# Test6502_project.net
KiCad netlist of a schematic drawn in Altium Designer
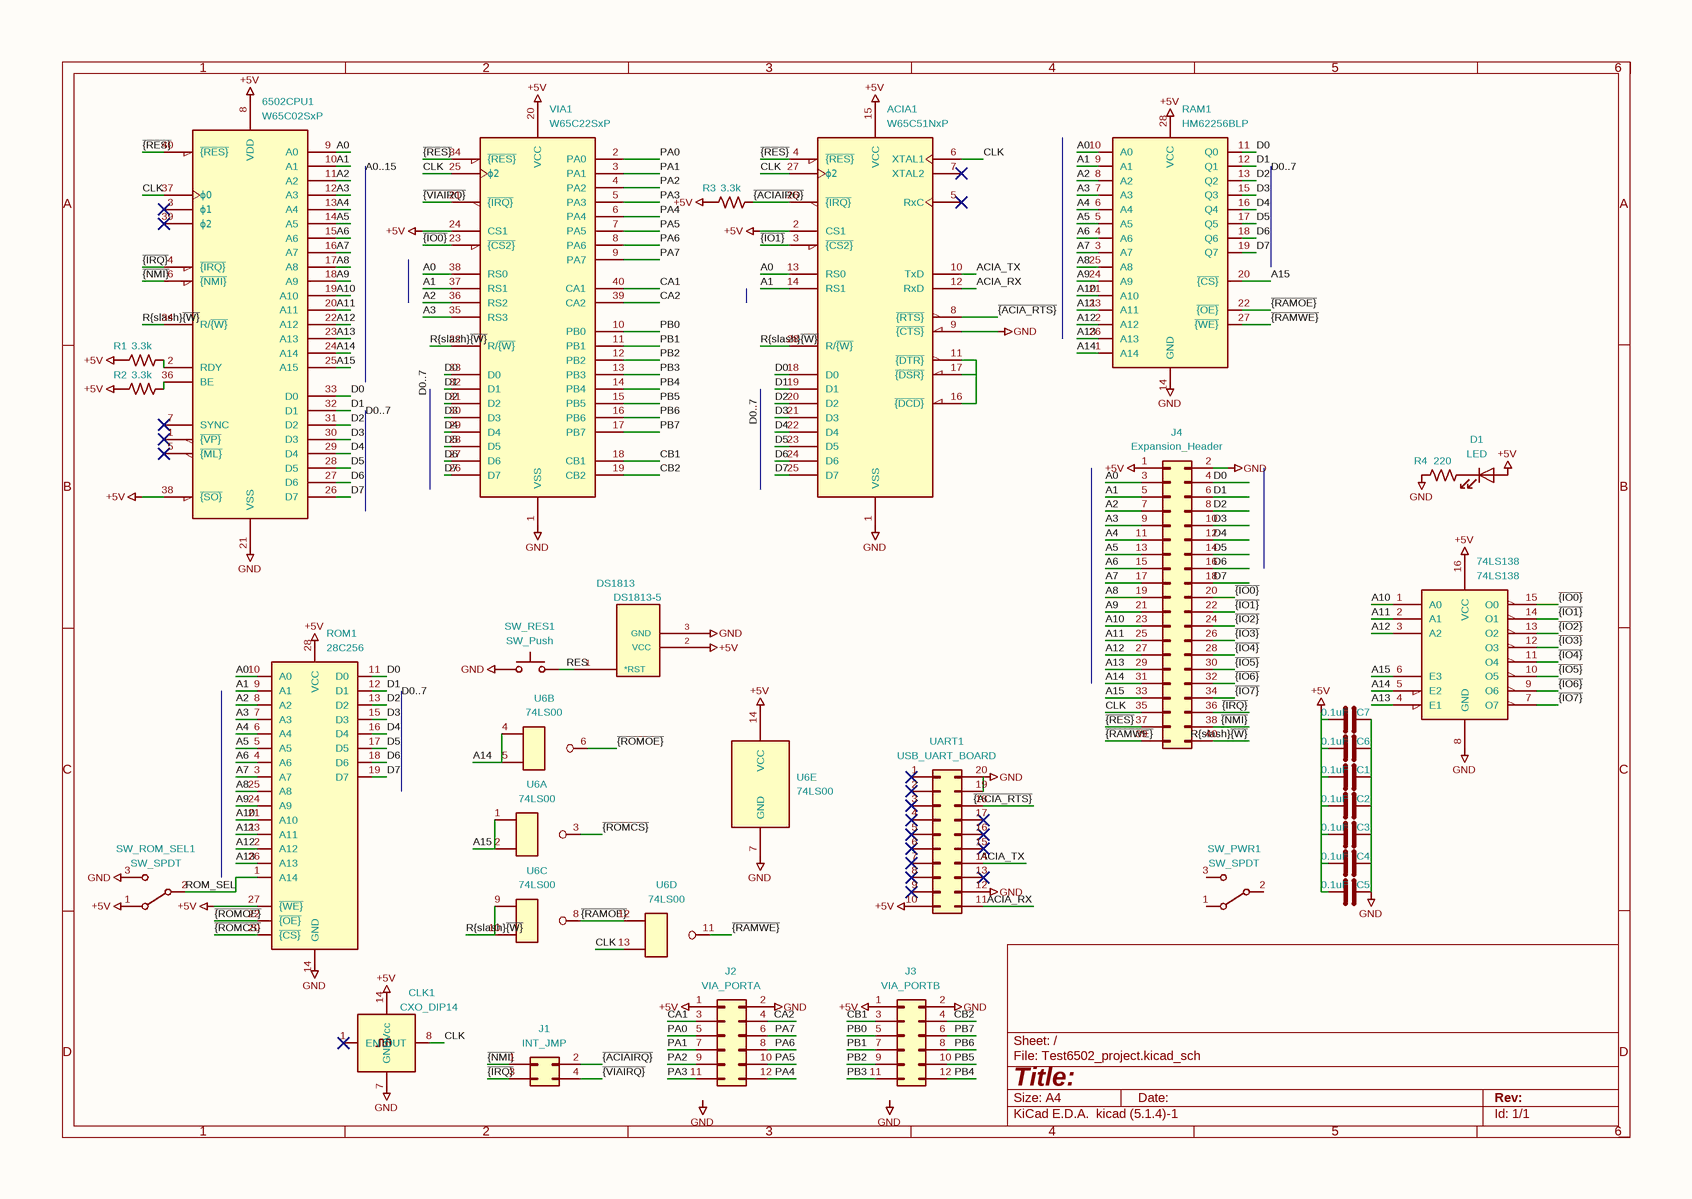
[diagram p0: Test6502_project.SchDoc]

(export (version "E")
  (design (tool "Eeschema 10.0.6"))
  (components
    (comp (ref "74LS138") (value "74LS138") (libsource (lib "74xx") (part "74LS138")))
    (comp (ref "6502CPU1") (value "W65C02SxP") (libsource (lib "65xx") (part "W65C02SxP")))
    (comp (ref "ACIA1") (value "W65C51NxP") (libsource (lib "65xx") (part "W65C51NxP")))
    (comp (ref "C1") (value "0.1uF") (libsource (lib "Device") (part "C")))
    (comp (ref "C2") (value "0.1uF") (libsource (lib "Device") (part "C")))
    (comp (ref "C3") (value "0.1uF") (libsource (lib "Device") (part "C")))
    (comp (ref "C4") (value "0.1uF") (libsource (lib "Device") (part "C")))
    (comp (ref "C5") (value "0.1uF") (libsource (lib "Device") (part "C")))
    (comp (ref "C6") (value "0.1uF") (libsource (lib "Device") (part "C")))
    (comp (ref "C7") (value "0.1uF") (libsource (lib "Device") (part "C")))
    (comp (ref "CLK1") (value "CXO_DIP14") (libsource (lib "Oscillator") (part "CXO_DIP14")))
    (comp (ref "D1") (value "LED") (libsource (lib "Device") (part "LED")))
    (comp (ref "DS1813")
      (value "DS1813-5")
      (fields (field (name "MANUFACTURER_PART_NUMBER") "ds18135+"))
      (libsource (lib "DS1813-5") (part "DS1813-5"))
    )
    (comp (ref "J1") (value "INT_JMP") (libsource (lib "Connector_Generic") (part "Conn_02x02_Odd_Even")))
    (comp (ref "J2") (value "VIA_PORTA") (libsource (lib "Connector_Generic") (part "Conn_02x06_Odd_Even")))
    (comp (ref "J3") (value "VIA_PORTB") (libsource (lib "Connector_Generic") (part "Conn_02x06_Odd_Even")))
    (comp (ref "J4")
      (value "Expansion_Header")
      (libsource (lib "Connector_Generic") (part "Conn_02x20_Odd_Even"))
    )
    (comp (ref "R1") (value "3.3k") (libsource (lib "Device") (part "R_US")))
    (comp (ref "R2") (value "3.3k") (libsource (lib "Device") (part "R_US")))
    (comp (ref "R3") (value "3.3k") (libsource (lib "Device") (part "R_US")))
    (comp (ref "R4") (value "220") (libsource (lib "Device") (part "R_US")))
    (comp (ref "RAM1") (value "HM62256BLP") (libsource (lib "Memory_RAM") (part "HM62256BLP")))
    (comp (ref "ROM1") (value "28C256") (libsource (lib "Memory_EEPROM") (part "28C256")))
    (comp (ref "SW_PWR1") (value "SW_SPDT") (libsource (lib "Switch") (part "SW_SPDT")))
    (comp (ref "SW_RES1") (value "SW_Push") (libsource (lib "Switch") (part "SW_Push")))
    (comp (ref "SW_ROM_SEL1") (value "SW_SPDT") (libsource (lib "Switch") (part "SW_SPDT")))
    (comp (ref "U6") (value "74LS00") (libsource (lib "74xx") (part "74LS00")))
    (comp (ref "UART1")
      (value "USB_UART_BOARD")
      (libsource (lib "Connector_Generic") (part "Conn_02x10_Counter_Clockwise"))
    )
    (comp (ref "VIA1") (value "W65C22SxP") (libsource (lib "65xx") (part "W65C22SxP")))
  )
  (nets
    (net (code "3") (name "+5V") (class "Default")
      (node (ref "6502CPU1") (pin "38") (pinfunction "~{{SO}}_38") (pintype "passive"))
      (node (ref "6502CPU1") (pin "8") (pinfunction "VDD_8") (pintype "passive"))
      (node (ref "74LS138") (pin "16") (pinfunction "VCC_16") (pintype "passive"))
      (node (ref "ACIA1") (pin "15") (pinfunction "VCC_15") (pintype "passive"))
      (node (ref "ACIA1") (pin "2") (pinfunction "CS1_2") (pintype "passive"))
      (node (ref "C1") (pin "1") (pinfunction "1_1") (pintype "passive"))
      (node (ref "C2") (pin "1") (pinfunction "1_1") (pintype "passive"))
      (node (ref "C3") (pin "1") (pinfunction "1_1") (pintype "passive"))
      (node (ref "C4") (pin "1") (pinfunction "1_1") (pintype "passive"))
      (node (ref "C5") (pin "1") (pinfunction "1_1") (pintype "passive"))
      (node (ref "C6") (pin "1") (pinfunction "1_1") (pintype "passive"))
      (node (ref "C7") (pin "1") (pinfunction "1_1") (pintype "passive"))
      (node (ref "CLK1") (pin "14") (pinfunction "Vcc_14") (pintype "passive"))
      (node (ref "D1") (pin "2") (pinfunction "A_2") (pintype "passive"))
      (node (ref "DS1813") (pin "2") (pinfunction "VCC_2") (pintype "passive"))
      (node (ref "J2") (pin "1") (pinfunction "Pin_1_1") (pintype "passive"))
      (node (ref "J3") (pin "1") (pinfunction "Pin_1_1") (pintype "passive"))
      (node (ref "J4") (pin "1") (pinfunction "Pin_1_1") (pintype "passive"))
      (node (ref "R1") (pin "1") (pinfunction "1_1") (pintype "passive"))
      (node (ref "R2") (pin "1") (pinfunction "1_1") (pintype "passive"))
      (node (ref "R3") (pin "1") (pinfunction "1_1") (pintype "passive"))
      (node (ref "RAM1") (pin "28") (pinfunction "VCC_28") (pintype "passive"))
      (node (ref "ROM1") (pin "27") (pinfunction "~{{WE}}_27") (pintype "passive"))
      (node (ref "ROM1") (pin "28") (pinfunction "VCC_28") (pintype "passive"))
      (node (ref "SW_ROM_SEL1") (pin "1") (pinfunction "A_1") (pintype "passive"))
      (node (ref "U6") (pin "14") (pinfunction "VCC_14") (pintype "passive"))
      (node (ref "UART1") (pin "10") (pinfunction "Pin_10_10") (pintype "passive"))
      (node (ref "VIA1") (pin "20") (pinfunction "VCC_20") (pintype "passive"))
      (node (ref "VIA1") (pin "24") (pinfunction "CS1_24") (pintype "passive"))
    )
    (net (code "4") (name "/A0") (class "Default")
      (node (ref "6502CPU1") (pin "9") (pinfunction "A0_9") (pintype "passive"))
      (node (ref "ACIA1") (pin "13") (pinfunction "RS0_13") (pintype "passive"))
      (node (ref "J4") (pin "3") (pinfunction "Pin_3_3") (pintype "passive"))
      (node (ref "RAM1") (pin "10") (pinfunction "A0_10") (pintype "passive"))
      (node (ref "ROM1") (pin "10") (pinfunction "A0_10") (pintype "passive"))
      (node (ref "VIA1") (pin "38") (pinfunction "RS0_38") (pintype "passive"))
    )
    (net (code "5") (name "/A1") (class "Default")
      (node (ref "6502CPU1") (pin "10") (pinfunction "A1_10") (pintype "passive"))
      (node (ref "ACIA1") (pin "14") (pinfunction "RS1_14") (pintype "passive"))
      (node (ref "J4") (pin "5") (pinfunction "Pin_5_5") (pintype "passive"))
      (node (ref "RAM1") (pin "9") (pinfunction "A1_9") (pintype "passive"))
      (node (ref "ROM1") (pin "9") (pinfunction "A1_9") (pintype "passive"))
      (node (ref "VIA1") (pin "37") (pinfunction "RS1_37") (pintype "passive"))
    )
    (net (code "6") (name "/A2") (class "Default")
      (node (ref "6502CPU1") (pin "11") (pinfunction "A2_11") (pintype "passive"))
      (node (ref "J4") (pin "7") (pinfunction "Pin_7_7") (pintype "passive"))
      (node (ref "RAM1") (pin "8") (pinfunction "A2_8") (pintype "passive"))
      (node (ref "ROM1") (pin "8") (pinfunction "A2_8") (pintype "passive"))
      (node (ref "VIA1") (pin "36") (pinfunction "RS2_36") (pintype "passive"))
    )
    (net (code "7") (name "/A3") (class "Default")
      (node (ref "6502CPU1") (pin "12") (pinfunction "A3_12") (pintype "passive"))
      (node (ref "J4") (pin "9") (pinfunction "Pin_9_9") (pintype "passive"))
      (node (ref "RAM1") (pin "7") (pinfunction "A3_7") (pintype "passive"))
      (node (ref "ROM1") (pin "7") (pinfunction "A3_7") (pintype "passive"))
      (node (ref "VIA1") (pin "35") (pinfunction "RS3_35") (pintype "passive"))
    )
    (net (code "8") (name "/A4") (class "Default")
      (node (ref "6502CPU1") (pin "13") (pinfunction "A4_13") (pintype "passive"))
      (node (ref "J4") (pin "11") (pinfunction "Pin_11_11") (pintype "passive"))
      (node (ref "RAM1") (pin "6") (pinfunction "A4_6") (pintype "passive"))
      (node (ref "ROM1") (pin "6") (pinfunction "A4_6") (pintype "passive"))
    )
    (net (code "9") (name "/A5") (class "Default")
      (node (ref "6502CPU1") (pin "14") (pinfunction "A5_14") (pintype "passive"))
      (node (ref "J4") (pin "13") (pinfunction "Pin_13_13") (pintype "passive"))
      (node (ref "RAM1") (pin "5") (pinfunction "A5_5") (pintype "passive"))
      (node (ref "ROM1") (pin "5") (pinfunction "A5_5") (pintype "passive"))
    )
    (net (code "10") (name "/A6") (class "Default")
      (node (ref "6502CPU1") (pin "15") (pinfunction "A6_15") (pintype "passive"))
      (node (ref "J4") (pin "15") (pinfunction "Pin_15_15") (pintype "passive"))
      (node (ref "RAM1") (pin "4") (pinfunction "A6_4") (pintype "passive"))
      (node (ref "ROM1") (pin "4") (pinfunction "A6_4") (pintype "passive"))
    )
    (net (code "11") (name "/A7") (class "Default")
      (node (ref "6502CPU1") (pin "16") (pinfunction "A7_16") (pintype "passive"))
      (node (ref "J4") (pin "17") (pinfunction "Pin_17_17") (pintype "passive"))
      (node (ref "RAM1") (pin "3") (pinfunction "A7_3") (pintype "passive"))
      (node (ref "ROM1") (pin "3") (pinfunction "A7_3") (pintype "passive"))
    )
    (net (code "12") (name "/A8") (class "Default")
      (node (ref "6502CPU1") (pin "17") (pinfunction "A8_17") (pintype "passive"))
      (node (ref "J4") (pin "19") (pinfunction "Pin_19_19") (pintype "passive"))
      (node (ref "RAM1") (pin "25") (pinfunction "A8_25") (pintype "passive"))
      (node (ref "ROM1") (pin "25") (pinfunction "A8_25") (pintype "passive"))
    )
    (net (code "13") (name "/A9") (class "Default")
      (node (ref "6502CPU1") (pin "18") (pinfunction "A9_18") (pintype "passive"))
      (node (ref "J4") (pin "21") (pinfunction "Pin_21_21") (pintype "passive"))
      (node (ref "RAM1") (pin "24") (pinfunction "A9_24") (pintype "passive"))
      (node (ref "ROM1") (pin "24") (pinfunction "A9_24") (pintype "passive"))
    )
    (net (code "14") (name "/A10") (class "Default")
      (node (ref "6502CPU1") (pin "19") (pinfunction "A10_19") (pintype "passive"))
      (node (ref "74LS138") (pin "1") (pinfunction "A0_1") (pintype "passive"))
      (node (ref "J4") (pin "23") (pinfunction "Pin_23_23") (pintype "passive"))
      (node (ref "RAM1") (pin "21") (pinfunction "A10_21") (pintype "passive"))
      (node (ref "ROM1") (pin "21") (pinfunction "A10_21") (pintype "passive"))
    )
    (net (code "15") (name "/A11") (class "Default")
      (node (ref "6502CPU1") (pin "20") (pinfunction "A11_20") (pintype "passive"))
      (node (ref "74LS138") (pin "2") (pinfunction "A1_2") (pintype "passive"))
      (node (ref "J4") (pin "25") (pinfunction "Pin_25_25") (pintype "passive"))
      (node (ref "RAM1") (pin "23") (pinfunction "A11_23") (pintype "passive"))
      (node (ref "ROM1") (pin "23") (pinfunction "A11_23") (pintype "passive"))
    )
    (net (code "16") (name "/A12") (class "Default")
      (node (ref "6502CPU1") (pin "22") (pinfunction "A12_22") (pintype "passive"))
      (node (ref "74LS138") (pin "3") (pinfunction "A2_3") (pintype "passive"))
      (node (ref "J4") (pin "27") (pinfunction "Pin_27_27") (pintype "passive"))
      (node (ref "RAM1") (pin "2") (pinfunction "A12_2") (pintype "passive"))
      (node (ref "ROM1") (pin "2") (pinfunction "A12_2") (pintype "passive"))
    )
    (net (code "17") (name "/A13") (class "Default")
      (node (ref "6502CPU1") (pin "23") (pinfunction "A13_23") (pintype "passive"))
      (node (ref "74LS138") (pin "4") (pinfunction "E1_4") (pintype "passive"))
      (node (ref "J4") (pin "29") (pinfunction "Pin_29_29") (pintype "passive"))
      (node (ref "RAM1") (pin "26") (pinfunction "A13_26") (pintype "passive"))
      (node (ref "ROM1") (pin "26") (pinfunction "A13_26") (pintype "passive"))
    )
    (net (code "18") (name "/A14") (class "Default")
      (node (ref "6502CPU1") (pin "24") (pinfunction "A14_24") (pintype "passive"))
      (node (ref "74LS138") (pin "5") (pinfunction "E2_5") (pintype "passive"))
      (node (ref "J4") (pin "31") (pinfunction "Pin_31_31") (pintype "passive"))
      (node (ref "RAM1") (pin "1") (pinfunction "A14_1") (pintype "passive"))
      (node (ref "U6") (pin "4") (pinfunction "4_4") (pintype "passive"))
      (node (ref "U6") (pin "5") (pinfunction "5_5") (pintype "passive"))
    )
    (net (code "19") (name "/A15") (class "Default")
      (node (ref "6502CPU1") (pin "25") (pinfunction "A15_25") (pintype "passive"))
      (node (ref "74LS138") (pin "6") (pinfunction "E3_6") (pintype "passive"))
      (node (ref "J4") (pin "33") (pinfunction "Pin_33_33") (pintype "passive"))
      (node (ref "RAM1") (pin "20") (pinfunction "~{{CS}}_20") (pintype "passive"))
      (node (ref "U6") (pin "1") (pinfunction "1_1") (pintype "passive"))
      (node (ref "U6") (pin "2") (pinfunction "2_2") (pintype "passive"))
    )
    (net (code "20") (name "/ACIA_RX") (class "Default")
      (node (ref "ACIA1") (pin "12") (pinfunction "RxD_12") (pintype "passive"))
      (node (ref "UART1") (pin "11") (pinfunction "Pin_11_11") (pintype "passive"))
    )
    (net (code "21") (name "/ACIA_TX") (class "Default")
      (node (ref "ACIA1") (pin "10") (pinfunction "TxD_10") (pintype "passive"))
      (node (ref "UART1") (pin "14") (pinfunction "Pin_14_14") (pintype "passive"))
    )
    (net (code "22") (name "/CA1") (class "Default")
      (node (ref "J2") (pin "3") (pinfunction "Pin_3_3") (pintype "passive"))
      (node (ref "VIA1") (pin "40") (pinfunction "CA1_40") (pintype "passive"))
    )
    (net (code "23") (name "/CA2") (class "Default")
      (node (ref "J2") (pin "4") (pinfunction "Pin_4_4") (pintype "passive"))
      (node (ref "VIA1") (pin "39") (pinfunction "CA2_39") (pintype "passive"))
    )
    (net (code "24") (name "/CB1") (class "Default")
      (node (ref "J3") (pin "3") (pinfunction "Pin_3_3") (pintype "passive"))
      (node (ref "VIA1") (pin "18") (pinfunction "CB1_18") (pintype "passive"))
    )
    (net (code "25") (name "/CB2") (class "Default")
      (node (ref "J3") (pin "4") (pinfunction "Pin_4_4") (pintype "passive"))
      (node (ref "VIA1") (pin "19") (pinfunction "CB2_19") (pintype "passive"))
    )
    (net (code "26") (name "/CLK") (class "Default")
      (node (ref "6502CPU1") (pin "37") (pinfunction "ϕ0_37") (pintype "passive"))
      (node (ref "ACIA1") (pin "27") (pinfunction "ϕ2_27") (pintype "passive"))
      (node (ref "ACIA1") (pin "6") (pinfunction "XTAL1_6") (pintype "passive"))
      (node (ref "CLK1") (pin "8") (pinfunction "OUT_8") (pintype "passive"))
      (node (ref "J4") (pin "35") (pinfunction "Pin_35_35") (pintype "passive"))
      (node (ref "U6") (pin "13") (pinfunction "13_13") (pintype "passive"))
      (node (ref "VIA1") (pin "25") (pinfunction "ϕ2_25") (pintype "passive"))
    )
    (net (code "27") (name "/D0") (class "Default")
      (node (ref "6502CPU1") (pin "33") (pinfunction "D0_33") (pintype "passive"))
      (node (ref "ACIA1") (pin "18") (pinfunction "D0_18") (pintype "passive"))
      (node (ref "J4") (pin "4") (pinfunction "Pin_4_4") (pintype "passive"))
      (node (ref "RAM1") (pin "11") (pinfunction "Q0_11") (pintype "passive"))
      (node (ref "ROM1") (pin "11") (pinfunction "D0_11") (pintype "passive"))
      (node (ref "VIA1") (pin "33") (pinfunction "D0_33") (pintype "passive"))
    )
    (net (code "28") (name "/D1") (class "Default")
      (node (ref "6502CPU1") (pin "32") (pinfunction "D1_32") (pintype "passive"))
      (node (ref "ACIA1") (pin "19") (pinfunction "D1_19") (pintype "passive"))
      (node (ref "J4") (pin "6") (pinfunction "Pin_6_6") (pintype "passive"))
      (node (ref "RAM1") (pin "12") (pinfunction "Q1_12") (pintype "passive"))
      (node (ref "ROM1") (pin "12") (pinfunction "D1_12") (pintype "passive"))
      (node (ref "VIA1") (pin "32") (pinfunction "D1_32") (pintype "passive"))
    )
    (net (code "29") (name "/D2") (class "Default")
      (node (ref "6502CPU1") (pin "31") (pinfunction "D2_31") (pintype "passive"))
      (node (ref "ACIA1") (pin "20") (pinfunction "D2_20") (pintype "passive"))
      (node (ref "J4") (pin "8") (pinfunction "Pin_8_8") (pintype "passive"))
      (node (ref "RAM1") (pin "13") (pinfunction "Q2_13") (pintype "passive"))
      (node (ref "ROM1") (pin "13") (pinfunction "D2_13") (pintype "passive"))
      (node (ref "VIA1") (pin "31") (pinfunction "D2_31") (pintype "passive"))
    )
    (net (code "30") (name "/D3") (class "Default")
      (node (ref "6502CPU1") (pin "30") (pinfunction "D3_30") (pintype "passive"))
      (node (ref "ACIA1") (pin "21") (pinfunction "D3_21") (pintype "passive"))
      (node (ref "J4") (pin "10") (pinfunction "Pin_10_10") (pintype "passive"))
      (node (ref "RAM1") (pin "15") (pinfunction "Q3_15") (pintype "passive"))
      (node (ref "ROM1") (pin "15") (pinfunction "D3_15") (pintype "passive"))
      (node (ref "VIA1") (pin "30") (pinfunction "D3_30") (pintype "passive"))
    )
    (net (code "31") (name "/D4") (class "Default")
      (node (ref "6502CPU1") (pin "29") (pinfunction "D4_29") (pintype "passive"))
      (node (ref "ACIA1") (pin "22") (pinfunction "D4_22") (pintype "passive"))
      (node (ref "J4") (pin "12") (pinfunction "Pin_12_12") (pintype "passive"))
      (node (ref "RAM1") (pin "16") (pinfunction "Q4_16") (pintype "passive"))
      (node (ref "ROM1") (pin "16") (pinfunction "D4_16") (pintype "passive"))
      (node (ref "VIA1") (pin "29") (pinfunction "D4_29") (pintype "passive"))
    )
    (net (code "32") (name "/D5") (class "Default")
      (node (ref "6502CPU1") (pin "28") (pinfunction "D5_28") (pintype "passive"))
      (node (ref "ACIA1") (pin "23") (pinfunction "D5_23") (pintype "passive"))
      (node (ref "J4") (pin "14") (pinfunction "Pin_14_14") (pintype "passive"))
      (node (ref "RAM1") (pin "17") (pinfunction "Q5_17") (pintype "passive"))
      (node (ref "ROM1") (pin "17") (pinfunction "D5_17") (pintype "passive"))
      (node (ref "VIA1") (pin "28") (pinfunction "D5_28") (pintype "passive"))
    )
    (net (code "33") (name "/D6") (class "Default")
      (node (ref "6502CPU1") (pin "27") (pinfunction "D6_27") (pintype "passive"))
      (node (ref "ACIA1") (pin "24") (pinfunction "D6_24") (pintype "passive"))
      (node (ref "J4") (pin "16") (pinfunction "Pin_16_16") (pintype "passive"))
      (node (ref "RAM1") (pin "18") (pinfunction "Q6_18") (pintype "passive"))
      (node (ref "ROM1") (pin "18") (pinfunction "D6_18") (pintype "passive"))
      (node (ref "VIA1") (pin "27") (pinfunction "D6_27") (pintype "passive"))
    )
    (net (code "34") (name "/D7") (class "Default")
      (node (ref "6502CPU1") (pin "26") (pinfunction "D7_26") (pintype "passive"))
      (node (ref "ACIA1") (pin "25") (pinfunction "D7_25") (pintype "passive"))
      (node (ref "J4") (pin "18") (pinfunction "Pin_18_18") (pintype "passive"))
      (node (ref "RAM1") (pin "19") (pinfunction "Q7_19") (pintype "passive"))
      (node (ref "ROM1") (pin "19") (pinfunction "D7_19") (pintype "passive"))
      (node (ref "VIA1") (pin "26") (pinfunction "D7_26") (pintype "passive"))
    )
    (net (code "35") (name "/PA0") (class "Default")
      (node (ref "J2") (pin "5") (pinfunction "Pin_5_5") (pintype "passive"))
      (node (ref "VIA1") (pin "2") (pinfunction "PA0_2") (pintype "passive"))
    )
    (net (code "36") (name "/PA1") (class "Default")
      (node (ref "J2") (pin "7") (pinfunction "Pin_7_7") (pintype "passive"))
      (node (ref "VIA1") (pin "3") (pinfunction "PA1_3") (pintype "passive"))
    )
    (net (code "37") (name "/PA2") (class "Default")
      (node (ref "J2") (pin "9") (pinfunction "Pin_9_9") (pintype "passive"))
      (node (ref "VIA1") (pin "4") (pinfunction "PA2_4") (pintype "passive"))
    )
    (net (code "38") (name "/PA3") (class "Default")
      (node (ref "J2") (pin "11") (pinfunction "Pin_11_11") (pintype "passive"))
      (node (ref "VIA1") (pin "5") (pinfunction "PA3_5") (pintype "passive"))
    )
    (net (code "39") (name "/PA4") (class "Default")
      (node (ref "J2") (pin "12") (pinfunction "Pin_12_12") (pintype "passive"))
      (node (ref "VIA1") (pin "6") (pinfunction "PA4_6") (pintype "passive"))
    )
    (net (code "40") (name "/PA5") (class "Default")
      (node (ref "J2") (pin "10") (pinfunction "Pin_10_10") (pintype "passive"))
      (node (ref "VIA1") (pin "7") (pinfunction "PA5_7") (pintype "passive"))
    )
    (net (code "41") (name "/PA6") (class "Default")
      (node (ref "J2") (pin "8") (pinfunction "Pin_8_8") (pintype "passive"))
      (node (ref "VIA1") (pin "8") (pinfunction "PA6_8") (pintype "passive"))
    )
    (net (code "42") (name "/PA7") (class "Default")
      (node (ref "J2") (pin "6") (pinfunction "Pin_6_6") (pintype "passive"))
      (node (ref "VIA1") (pin "9") (pinfunction "PA7_9") (pintype "passive"))
    )
    (net (code "43") (name "/PB0") (class "Default")
      (node (ref "J3") (pin "5") (pinfunction "Pin_5_5") (pintype "passive"))
      (node (ref "VIA1") (pin "10") (pinfunction "PB0_10") (pintype "passive"))
    )
    (net (code "44") (name "/PB1") (class "Default")
      (node (ref "J3") (pin "7") (pinfunction "Pin_7_7") (pintype "passive"))
      (node (ref "VIA1") (pin "11") (pinfunction "PB1_11") (pintype "passive"))
    )
    (net (code "45") (name "/PB2") (class "Default")
      (node (ref "J3") (pin "9") (pinfunction "Pin_9_9") (pintype "passive"))
      (node (ref "VIA1") (pin "12") (pinfunction "PB2_12") (pintype "passive"))
    )
    (net (code "46") (name "/PB3") (class "Default")
      (node (ref "J3") (pin "11") (pinfunction "Pin_11_11") (pintype "passive"))
      (node (ref "VIA1") (pin "13") (pinfunction "PB3_13") (pintype "passive"))
    )
    (net (code "47") (name "/PB4") (class "Default")
      (node (ref "J3") (pin "12") (pinfunction "Pin_12_12") (pintype "passive"))
      (node (ref "VIA1") (pin "14") (pinfunction "PB4_14") (pintype "passive"))
    )
    (net (code "48") (name "/PB5") (class "Default")
      (node (ref "J3") (pin "10") (pinfunction "Pin_10_10") (pintype "passive"))
      (node (ref "VIA1") (pin "15") (pinfunction "PB5_15") (pintype "passive"))
    )
    (net (code "49") (name "/PB6") (class "Default")
      (node (ref "J3") (pin "8") (pinfunction "Pin_8_8") (pintype "passive"))
      (node (ref "VIA1") (pin "16") (pinfunction "PB6_16") (pintype "passive"))
    )
    (net (code "50") (name "/PB7") (class "Default")
      (node (ref "J3") (pin "6") (pinfunction "Pin_6_6") (pintype "passive"))
      (node (ref "VIA1") (pin "17") (pinfunction "PB7_17") (pintype "passive"))
    )
    (net (code "51") (name "/RES") (class "Default")
      (node (ref "DS1813") (pin "1") (pinfunction "*RST_1") (pintype "passive"))
      (node (ref "SW_RES1") (pin "2") (pinfunction "2_2") (pintype "passive"))
    )
    (net (code "52") (name "/ROM_SEL") (class "Default")
      (node (ref "ROM1") (pin "1") (pinfunction "A14_1") (pintype "passive"))
      (node (ref "SW_ROM_SEL1") (pin "2") (pinfunction "B_2") (pintype "passive"))
    )
    (net (code "53") (name "/R{slash}~{{W}}") (class "Default")
      (node (ref "6502CPU1") (pin "34") (pinfunction "R/~{{W}}_34") (pintype "passive"))
      (node (ref "ACIA1") (pin "28") (pinfunction "R/~{{W}}_28") (pintype "passive"))
      (node (ref "J4") (pin "40") (pinfunction "Pin_40_40") (pintype "passive"))
      (node (ref "U6") (pin "10") (pinfunction "10_10") (pintype "passive"))
      (node (ref "U6") (pin "9") (pinfunction "9_9") (pintype "passive"))
      (node (ref "VIA1") (pin "22") (pinfunction "R/~{{W}}_22") (pintype "passive"))
    )
    (net (code "56") (name "/~{{ACIAIRQ}}") (class "Default")
      (node (ref "ACIA1") (pin "26") (pinfunction "~{{IRQ}}_26") (pintype "passive"))
      (node (ref "J1") (pin "2") (pinfunction "Pin_2_2") (pintype "passive"))
      (node (ref "R3") (pin "2") (pinfunction "2_2") (pintype "passive"))
    )
    (net (code "57") (name "/~{{ACIA_RTS}}") (class "Default")
      (node (ref "ACIA1") (pin "8") (pinfunction "~{{RTS}}_8") (pintype "passive"))
      (node (ref "UART1") (pin "18") (pinfunction "Pin_18_18") (pintype "passive"))
    )
    (net (code "58") (name "/~{{IO0}}") (class "Default")
      (node (ref "74LS138") (pin "15") (pinfunction "O0_15") (pintype "passive"))
      (node (ref "J4") (pin "20") (pinfunction "Pin_20_20") (pintype "passive"))
      (node (ref "VIA1") (pin "23") (pinfunction "~{{CS2}}_23") (pintype "passive"))
    )
    (net (code "59") (name "/~{{IO1}}") (class "Default")
      (node (ref "74LS138") (pin "14") (pinfunction "O1_14") (pintype "passive"))
      (node (ref "ACIA1") (pin "3") (pinfunction "~{{CS2}}_3") (pintype "passive"))
      (node (ref "J4") (pin "22") (pinfunction "Pin_22_22") (pintype "passive"))
    )
    (net (code "60") (name "/~{{IO2}}") (class "Default")
      (node (ref "74LS138") (pin "13") (pinfunction "O2_13") (pintype "passive"))
      (node (ref "J4") (pin "24") (pinfunction "Pin_24_24") (pintype "passive"))
    )
    (net (code "61") (name "/~{{IO3}}") (class "Default")
      (node (ref "74LS138") (pin "12") (pinfunction "O3_12") (pintype "passive"))
      (node (ref "J4") (pin "26") (pinfunction "Pin_26_26") (pintype "passive"))
    )
    (net (code "62") (name "/~{{IO4}}") (class "Default")
      (node (ref "74LS138") (pin "11") (pinfunction "O4_11") (pintype "passive"))
      (node (ref "J4") (pin "28") (pinfunction "Pin_28_28") (pintype "passive"))
    )
    (net (code "63") (name "/~{{IO5}}") (class "Default")
      (node (ref "74LS138") (pin "10") (pinfunction "O5_10") (pintype "passive"))
      (node (ref "J4") (pin "30") (pinfunction "Pin_30_30") (pintype "passive"))
    )
    (net (code "64") (name "/~{{IO6}}") (class "Default")
      (node (ref "74LS138") (pin "9") (pinfunction "O6_9") (pintype "passive"))
      (node (ref "J4") (pin "32") (pinfunction "Pin_32_32") (pintype "passive"))
    )
    (net (code "65") (name "/~{{IO7}}") (class "Default")
      (node (ref "74LS138") (pin "7") (pinfunction "O7_7") (pintype "passive"))
      (node (ref "J4") (pin "34") (pinfunction "Pin_34_34") (pintype "passive"))
    )
    (net (code "66") (name "/~{{IRQ}}") (class "Default")
      (node (ref "6502CPU1") (pin "4") (pinfunction "~{{IRQ}}_4") (pintype "passive"))
      (node (ref "J1") (pin "3") (pinfunction "Pin_3_3") (pintype "passive"))
      (node (ref "J4") (pin "36") (pinfunction "Pin_36_36") (pintype "passive"))
    )
    (net (code "67") (name "/~{{NMI}}") (class "Default")
      (node (ref "6502CPU1") (pin "6") (pinfunction "~{{NMI}}_6") (pintype "passive"))
      (node (ref "J1") (pin "1") (pinfunction "Pin_1_1") (pintype "passive"))
      (node (ref "J4") (pin "38") (pinfunction "Pin_38_38") (pintype "passive"))
    )
    (net (code "68") (name "/~{{RAMOE}}") (class "Default")
      (node (ref "RAM1") (pin "22") (pinfunction "~{{OE}}_22") (pintype "passive"))
      (node (ref "U6") (pin "12") (pinfunction "12_12") (pintype "passive"))
      (node (ref "U6") (pin "8") (pinfunction "8_8") (pintype "passive"))
    )
    (net (code "69") (name "/~{{RAMWE}}") (class "Default")
      (node (ref "J4") (pin "39") (pinfunction "Pin_39_39") (pintype "passive"))
      (node (ref "RAM1") (pin "27") (pinfunction "~{{WE}}_27") (pintype "passive"))
      (node (ref "U6") (pin "11") (pinfunction "11_11") (pintype "passive"))
    )
    (net (code "70") (name "/~{{RES}}") (class "Default")
      (node (ref "6502CPU1") (pin "40") (pinfunction "~{{RES}}_40") (pintype "passive"))
      (node (ref "ACIA1") (pin "4") (pinfunction "~{{RES}}_4") (pintype "passive"))
      (node (ref "J4") (pin "37") (pinfunction "Pin_37_37") (pintype "passive"))
      (node (ref "VIA1") (pin "34") (pinfunction "~{{RES}}_34") (pintype "passive"))
    )
    (net (code "71") (name "/~{{ROMCS}}") (class "Default")
      (node (ref "ROM1") (pin "20") (pinfunction "~{{CS}}_20") (pintype "passive"))
      (node (ref "U6") (pin "3") (pinfunction "3_3") (pintype "passive"))
    )
    (net (code "72") (name "/~{{ROMOE}}") (class "Default")
      (node (ref "ROM1") (pin "22") (pinfunction "~{{OE}}_22") (pintype "passive"))
      (node (ref "U6") (pin "6") (pinfunction "6_6") (pintype "passive"))
    )
    (net (code "73") (name "/~{{VIAIRQ}}") (class "Default")
      (node (ref "J1") (pin "4") (pinfunction "Pin_4_4") (pintype "passive"))
      (node (ref "VIA1") (pin "21") (pinfunction "~{{IRQ}}_21") (pintype "passive"))
    )
    (net (code "74") (name "GND") (class "Default")
      (node (ref "6502CPU1") (pin "21") (pinfunction "VSS_21") (pintype "passive"))
      (node (ref "74LS138") (pin "8") (pinfunction "GND_8") (pintype "passive"))
      (node (ref "ACIA1") (pin "1") (pinfunction "VSS_1") (pintype "passive"))
      (node (ref "ACIA1") (pin "9") (pinfunction "~{{CTS}}_9") (pintype "passive"))
      (node (ref "C1") (pin "2") (pinfunction "2_2") (pintype "passive"))
      (node (ref "C2") (pin "2") (pinfunction "2_2") (pintype "passive"))
      (node (ref "C3") (pin "2") (pinfunction "2_2") (pintype "passive"))
      (node (ref "C4") (pin "2") (pinfunction "2_2") (pintype "passive"))
      (node (ref "C5") (pin "2") (pinfunction "2_2") (pintype "passive"))
      (node (ref "C6") (pin "2") (pinfunction "2_2") (pintype "passive"))
      (node (ref "C7") (pin "2") (pinfunction "2_2") (pintype "passive"))
      (node (ref "CLK1") (pin "7") (pinfunction "GND_7") (pintype "passive"))
      (node (ref "DS1813") (pin "3") (pinfunction "GND_3") (pintype "passive"))
      (node (ref "J2") (pin "2") (pinfunction "Pin_2_2") (pintype "passive"))
      (node (ref "J3") (pin "2") (pinfunction "Pin_2_2") (pintype "passive"))
      (node (ref "J4") (pin "2") (pinfunction "Pin_2_2") (pintype "passive"))
      (node (ref "R4") (pin "1") (pinfunction "1_1") (pintype "passive"))
      (node (ref "RAM1") (pin "14") (pinfunction "GND_14") (pintype "passive"))
      (node (ref "ROM1") (pin "14") (pinfunction "GND_14") (pintype "passive"))
      (node (ref "SW_RES1") (pin "1") (pinfunction "1_1") (pintype "passive"))
      (node (ref "SW_ROM_SEL1") (pin "3") (pinfunction "C_3") (pintype "passive"))
      (node (ref "U6") (pin "7") (pinfunction "GND_7") (pintype "passive"))
      (node (ref "UART1") (pin "12") (pinfunction "Pin_12_12") (pintype "passive"))
      (node (ref "UART1") (pin "19") (pinfunction "Pin_19_19") (pintype "passive"))
      (node (ref "UART1") (pin "20") (pinfunction "Pin_20_20") (pintype "passive"))
      (node (ref "VIA1") (pin "1") (pinfunction "VSS_1") (pintype "passive"))
    )
    (net (code "75") (name "Net-(6502CPU1-BE)") (class "Default")
      (node (ref "6502CPU1") (pin "36") (pinfunction "BE_36") (pintype "passive"))
      (node (ref "R2") (pin "2") (pinfunction "2_2") (pintype "passive"))
    )
    (net (code "76") (name "Net-(6502CPU1-RDY)") (class "Default")
      (node (ref "6502CPU1") (pin "2") (pinfunction "RDY_2") (pintype "passive"))
      (node (ref "R1") (pin "2") (pinfunction "2_2") (pintype "passive"))
    )
    (net (code "77") (name "Net-(ACIA1-~{{DCD}})") (class "Default")
      (node (ref "ACIA1") (pin "11") (pinfunction "~{{DTR}}_11") (pintype "passive"))
      (node (ref "ACIA1") (pin "16") (pinfunction "~{{DCD}}_16") (pintype "passive"))
      (node (ref "ACIA1") (pin "17") (pinfunction "~{{DSR}}_17") (pintype "passive"))
    )
    (net (code "78") (name "Net-(D1-K)") (class "Default")
      (node (ref "D1") (pin "1") (pinfunction "K_1") (pintype "passive"))
      (node (ref "R4") (pin "2") (pinfunction "2_2") (pintype "passive"))
    )
    (net (code "79") (name "unconnected-(6502CPU1-SYNC-Pad7)") (class "Default")
      (node (ref "6502CPU1") (pin "7") (pinfunction "SYNC_7") (pintype "passive+no_connect"))
    )
    (net (code "80") (name "unconnected-(6502CPU1-nc-Pad35)") (class "Default")
      (node (ref "6502CPU1") (pin "35") (pinfunction "nc_35") (pintype "passive"))
    )
    (net (code "81") (name "unconnected-(6502CPU1-~{{ML}}-Pad5)") (class "Default")
      (node (ref "6502CPU1") (pin "5") (pinfunction "~{{ML}}_5") (pintype "passive+no_connect"))
    )
    (net (code "82") (name "unconnected-(6502CPU1-~{{VP}}-Pad1)") (class "Default")
      (node (ref "6502CPU1") (pin "1") (pinfunction "~{{VP}}_1") (pintype "passive+no_connect"))
    )
    (net (code "83") (name "unconnected-(6502CPU1-ϕ1-Pad3)") (class "Default")
      (node (ref "6502CPU1") (pin "3") (pinfunction "ϕ1_3") (pintype "passive+no_connect"))
    )
    (net (code "84") (name "unconnected-(6502CPU1-ϕ2-Pad39)") (class "Default")
      (node (ref "6502CPU1") (pin "39") (pinfunction "ϕ2_39") (pintype "passive+no_connect"))
    )
    (net (code "85") (name "unconnected-(ACIA1-RxC-Pad5)") (class "Default")
      (node (ref "ACIA1") (pin "5") (pinfunction "RxC_5") (pintype "passive+no_connect"))
    )
    (net (code "86") (name "unconnected-(ACIA1-XTAL2-Pad7)") (class "Default")
      (node (ref "ACIA1") (pin "7") (pinfunction "XTAL2_7") (pintype "passive+no_connect"))
    )
    (net (code "87") (name "unconnected-(CLK1-EN-Pad1)") (class "Default")
      (node (ref "CLK1") (pin "1") (pinfunction "EN_1") (pintype "passive+no_connect"))
    )
    (net (code "88") (name "unconnected-(SW_PWR1-A-Pad1)") (class "Default")
      (node (ref "SW_PWR1") (pin "1") (pinfunction "A_1") (pintype "passive"))
    )
    (net (code "89") (name "unconnected-(SW_PWR1-B-Pad2)") (class "Default")
      (node (ref "SW_PWR1") (pin "2") (pinfunction "B_2") (pintype "passive"))
    )
    (net (code "90") (name "unconnected-(SW_PWR1-C-Pad3)") (class "Default")
      (node (ref "SW_PWR1") (pin "3") (pinfunction "C_3") (pintype "passive"))
    )
    (net (code "91") (name "unconnected-(UART1-Pin_1-Pad1)") (class "Default")
      (node (ref "UART1") (pin "1") (pinfunction "Pin_1_1") (pintype "passive+no_connect"))
    )
    (net (code "92") (name "unconnected-(UART1-Pin_2-Pad2)") (class "Default")
      (node (ref "UART1") (pin "2") (pinfunction "Pin_2_2") (pintype "passive+no_connect"))
    )
    (net (code "93") (name "unconnected-(UART1-Pin_3-Pad3)") (class "Default")
      (node (ref "UART1") (pin "3") (pinfunction "Pin_3_3") (pintype "passive+no_connect"))
    )
    (net (code "94") (name "unconnected-(UART1-Pin_4-Pad4)") (class "Default")
      (node (ref "UART1") (pin "4") (pinfunction "Pin_4_4") (pintype "passive+no_connect"))
    )
    (net (code "95") (name "unconnected-(UART1-Pin_5-Pad5)") (class "Default")
      (node (ref "UART1") (pin "5") (pinfunction "Pin_5_5") (pintype "passive+no_connect"))
    )
    (net (code "96") (name "unconnected-(UART1-Pin_6-Pad6)") (class "Default")
      (node (ref "UART1") (pin "6") (pinfunction "Pin_6_6") (pintype "passive+no_connect"))
    )
    (net (code "97") (name "unconnected-(UART1-Pin_7-Pad7)") (class "Default")
      (node (ref "UART1") (pin "7") (pinfunction "Pin_7_7") (pintype "passive+no_connect"))
    )
    (net (code "98") (name "unconnected-(UART1-Pin_8-Pad8)") (class "Default")
      (node (ref "UART1") (pin "8") (pinfunction "Pin_8_8") (pintype "passive+no_connect"))
    )
    (net (code "99") (name "unconnected-(UART1-Pin_9-Pad9)") (class "Default")
      (node (ref "UART1") (pin "9") (pinfunction "Pin_9_9") (pintype "passive+no_connect"))
    )
    (net (code "100") (name "unconnected-(UART1-Pin_13-Pad13)") (class "Default")
      (node (ref "UART1") (pin "13") (pinfunction "Pin_13_13") (pintype "passive+no_connect"))
    )
    (net (code "101") (name "unconnected-(UART1-Pin_15-Pad15)") (class "Default")
      (node (ref "UART1") (pin "15") (pinfunction "Pin_15_15") (pintype "passive+no_connect"))
    )
    (net (code "102") (name "unconnected-(UART1-Pin_16-Pad16)") (class "Default")
      (node (ref "UART1") (pin "16") (pinfunction "Pin_16_16") (pintype "passive+no_connect"))
    )
    (net (code "103") (name "unconnected-(UART1-Pin_17-Pad17)") (class "Default")
      (node (ref "UART1") (pin "17") (pinfunction "Pin_17_17") (pintype "passive+no_connect"))
    )
  )
)
